# design.net
KiCad netlist of a schematic drawn in Altium Designer
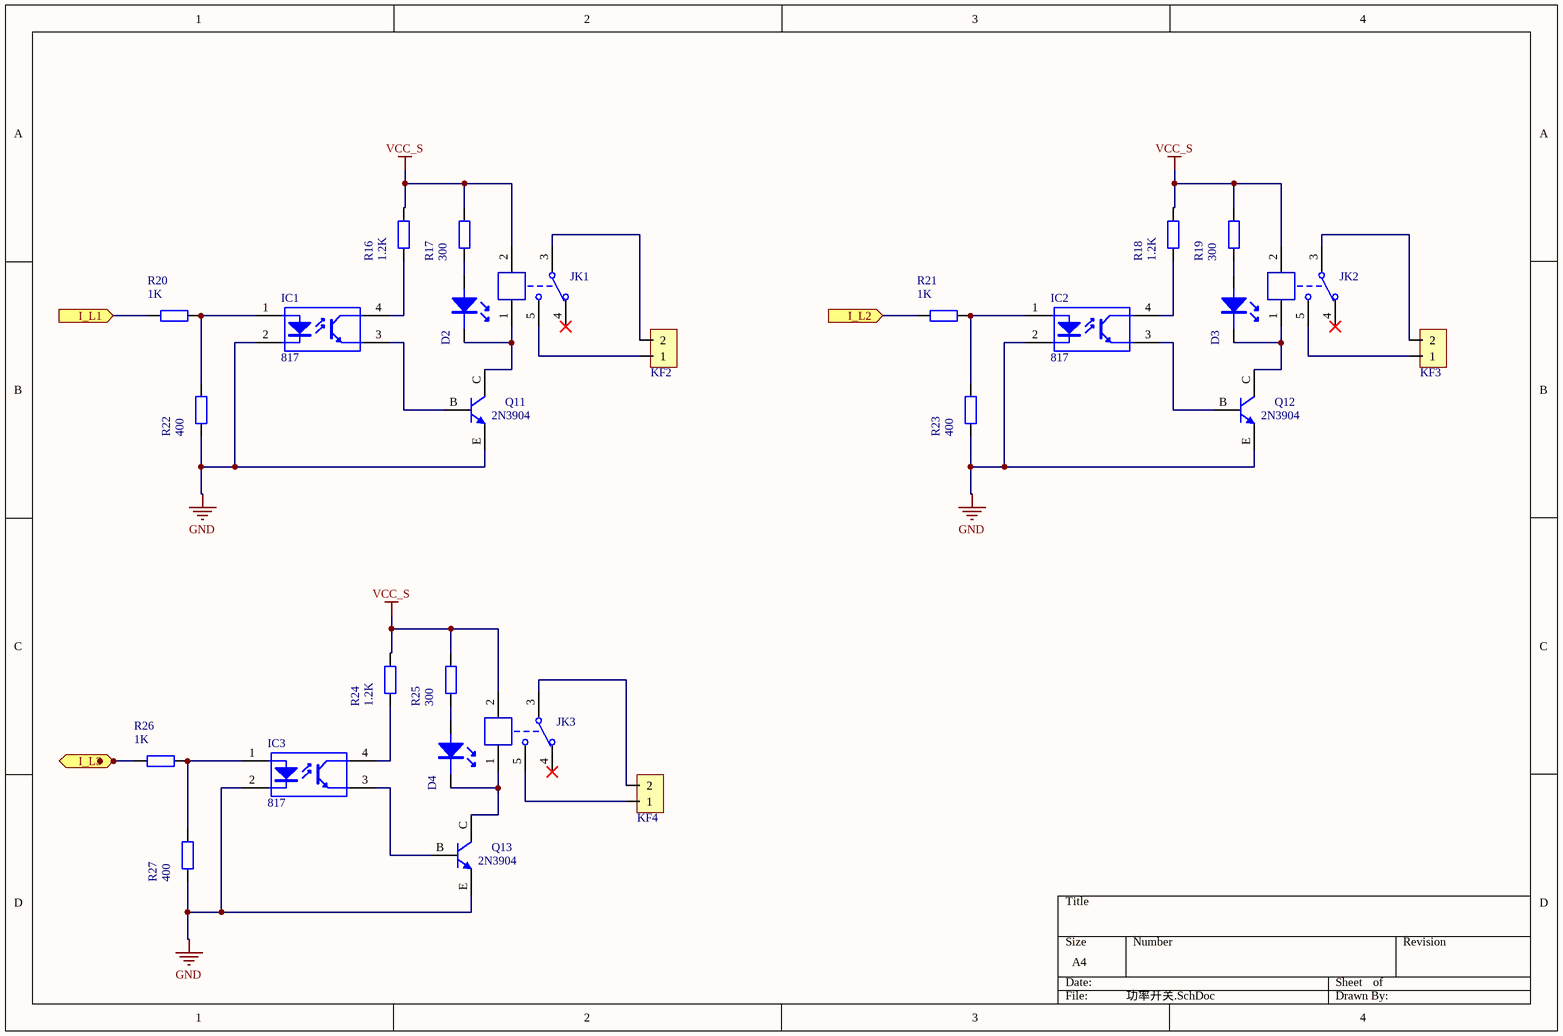
[diagram p0: 功率开关.SchDoc]

(export (version "E")
  (design (tool "Eeschema 10.0.6"))
  (components
    (comp (ref "D2")
      (value "C535A WJN CU0V0231")
      (footprint "LED2-D5X5")
      (description "DIP,封装/间距直径5/2.54mm,额定电压3.2V,亮度高亮,白色")
      (fields
        (field (name "PART NUMBER") "102DL-00002DG.01")
        (field (name "ALLOW ALTENATIVE PART") "Y")
        (field (name "REMARK") "Verified by CRD（张宗良） check list V1.0")
        (field (name "MODIFY TIME") "2017年01月07号")
        (field (name "APPROVED") "YES")
      )
      (libsource (lib "IA-04") (part "Diode-LED-2-N2"))
    )
    (comp (ref "D3")
      (value "C535A WJN CU0V0231")
      (footprint "LED2-D5X5")
      (description "DIP,封装/间距直径5/2.54mm,额定电压3.2V,亮度高亮,白色")
      (fields
        (field (name "PART NUMBER") "102DL-00002DG.01")
        (field (name "ALLOW ALTENATIVE PART") "Y")
        (field (name "REMARK") "Verified by CRD（张宗良） check list V1.0")
        (field (name "MODIFY TIME") "2017年01月07号")
        (field (name "APPROVED") "YES")
      )
      (libsource (lib "IA-04") (part "Diode-LED-2-N2"))
    )
    (comp (ref "D4")
      (value "C535A WJN CU0V0231")
      (footprint "LED2-D5X5")
      (description "DIP,封装/间距直径5/2.54mm,额定电压3.2V,亮度高亮,白色")
      (fields
        (field (name "PART NUMBER") "102DL-00002DG.01")
        (field (name "ALLOW ALTENATIVE PART") "Y")
        (field (name "REMARK") "Verified by CRD（张宗良） check list V1.0")
        (field (name "MODIFY TIME") "2017年01月07号")
        (field (name "APPROVED") "YES")
      )
      (libsource (lib "IA-04") (part "Diode-LED-2-N2"))
    )
    (comp (ref "IC1")
      (value "817")
      (footprint "DIP4-300")
      (description "线性光耦")
      (fields (field (name "版权归属") "源创客"))
      (libsource (lib "11.1 - 传感元件") (part "817"))
    )
    (comp (ref "IC2")
      (value "817")
      (footprint "DIP4-300")
      (description "线性光耦")
      (fields (field (name "版权归属") "源创客"))
      (libsource (lib "11.1 - 传感元件") (part "817"))
    )
    (comp (ref "IC3")
      (value "817")
      (footprint "DIP4-300")
      (description "线性光耦")
      (fields (field (name "版权归属") "源创客"))
      (libsource (lib "11.1 - 传感元件") (part "817"))
    )
    (comp (ref "JK1")
      (value "SRD-05VDC-SL-C")
      (footprint "SRD-C_B")
      (description "5V一组转换")
      (fields (field (name "版权归属") "源创客"))
      (libsource (lib "7.1   - 继电器") (part "SRD-05VDC-SL-C"))
    )
    (comp (ref "JK2")
      (value "SRD-05VDC-SL-C")
      (footprint "SRD-C_B")
      (description "5V一组转换")
      (fields (field (name "版权归属") "源创客"))
      (libsource (lib "7.1   - 继电器") (part "SRD-05VDC-SL-C"))
    )
    (comp (ref "JK3")
      (value "SRD-05VDC-SL-C")
      (footprint "SRD-C_B")
      (description "5V一组转换")
      (fields (field (name "版权归属") "源创客"))
      (libsource (lib "7.1   - 继电器") (part "SRD-05VDC-SL-C"))
    )
    (comp (ref "KF2")
      (value "KF301-5.08-2p")
      (footprint "KF301-5.0-2P")
      (libsource (lib "KF接口") (part "KF301"))
    )
    (comp (ref "KF3")
      (value "KF301-5.08-2p")
      (footprint "KF301-5.0-2P")
      (libsource (lib "KF接口") (part "KF301"))
    )
    (comp (ref "KF4")
      (value "KF301-5.08-2p")
      (footprint "KF301-5.0-2P")
      (libsource (lib "KF接口") (part "KF301"))
    )
    (comp (ref "Q11")
      (value "2N3904")
      (footprint "Triode:TO-92-3-EBC")
      (description "DIP,封装形式TO-92-3,耐压值40V,额定电流200mA,耗散功率625mW")
      (fields
        (field (name "PART NUMBER") "102GN-00009BA.01")
        (field (name "ALLOW ALTENATIVE PART") "Y")
        (field (name "REMARK") "Verified by BU1（吴明徽）check list V1.0")
        (field (name "MODIFY TIME") "2015年08月08号")
        (field (name "APPROVED") "YES")
      )
      (libsource (lib "IA-04") (part "Triode-NPN-BCE"))
    )
    (comp (ref "Q12")
      (value "2N3904")
      (footprint "Triode:TO-92-3-EBC")
      (description "DIP,封装形式TO-92-3,耐压值40V,额定电流200mA,耗散功率625mW")
      (fields
        (field (name "PART NUMBER") "102GN-00009BA.01")
        (field (name "ALLOW ALTENATIVE PART") "Y")
        (field (name "REMARK") "Verified by BU1（吴明徽）check list V1.0")
        (field (name "MODIFY TIME") "2015年08月08号")
        (field (name "APPROVED") "YES")
      )
      (libsource (lib "IA-04") (part "Triode-NPN-BCE"))
    )
    (comp (ref "Q13")
      (value "2N3904")
      (footprint "Triode:TO-92-3-EBC")
      (description "DIP,封装形式TO-92-3,耐压值40V,额定电流200mA,耗散功率625mW")
      (fields
        (field (name "PART NUMBER") "102GN-00009BA.01")
        (field (name "ALLOW ALTENATIVE PART") "Y")
        (field (name "REMARK") "Verified by BU1（吴明徽）check list V1.0")
        (field (name "MODIFY TIME") "2015年08月08号")
        (field (name "APPROVED") "YES")
      )
      (libsource (lib "IA-04") (part "Triode-NPN-BCE"))
    )
    (comp (ref "R16")
      (value "1.2K")
      (footprint "RY0R25W")
      (description "DIP,阻值1K,精度±0.1%,AXIAL0.4,额定功率1/4W")
      (fields
        (field (name "PART NUMBER") "102RO-00085BW.01")
        (field (name "ALLOW ALTENATIVE PART") "Y")
        (field (name "REMARK") "Verified by BU3（吴明徽）check list V1.0")
        (field (name "MODIFY TIME") "2015年11月30号")
        (field (name "APPROVED") "YES")
      )
      (libsource (lib "IA-04") (part "RES-2-NP"))
    )
    (comp (ref "R17")
      (value "300")
      (footprint "RY0R25W")
      (description "DIP,阻值1K,精度±0.1%,AXIAL0.4,额定功率1/4W")
      (fields
        (field (name "PART NUMBER") "102RO-00085BW.01")
        (field (name "ALLOW ALTENATIVE PART") "Y")
        (field (name "REMARK") "Verified by BU3（吴明徽）check list V1.0")
        (field (name "MODIFY TIME") "2015年11月30号")
        (field (name "APPROVED") "YES")
      )
      (libsource (lib "IA-04") (part "RES-2-NP"))
    )
    (comp (ref "R18")
      (value "1.2K")
      (footprint "RY0R25W")
      (description "DIP,阻值1K,精度±0.1%,AXIAL0.4,额定功率1/4W")
      (fields
        (field (name "PART NUMBER") "102RO-00085BW.01")
        (field (name "ALLOW ALTENATIVE PART") "Y")
        (field (name "REMARK") "Verified by BU3（吴明徽）check list V1.0")
        (field (name "MODIFY TIME") "2015年11月30号")
        (field (name "APPROVED") "YES")
      )
      (libsource (lib "IA-04") (part "RES-2-NP"))
    )
    (comp (ref "R19")
      (value "300")
      (footprint "RY0R25W")
      (description "DIP,阻值1K,精度±0.1%,AXIAL0.4,额定功率1/4W")
      (fields
        (field (name "PART NUMBER") "102RO-00085BW.01")
        (field (name "ALLOW ALTENATIVE PART") "Y")
        (field (name "REMARK") "Verified by BU3（吴明徽）check list V1.0")
        (field (name "MODIFY TIME") "2015年11月30号")
        (field (name "APPROVED") "YES")
      )
      (libsource (lib "IA-04") (part "RES-2-NP"))
    )
    (comp (ref "R20")
      (value "1K")
      (footprint "RY0R25W")
      (description "DIP,阻值1K,精度±0.1%,AXIAL0.4,额定功率1/4W")
      (fields
        (field (name "PART NUMBER") "102RO-00085BW.01")
        (field (name "ALLOW ALTENATIVE PART") "Y")
        (field (name "REMARK") "Verified by BU3（吴明徽）check list V1.0")
        (field (name "MODIFY TIME") "2015年11月30号")
        (field (name "APPROVED") "YES")
      )
      (libsource (lib "") (part "RES-2-NP_1"))
    )
    (comp (ref "R21")
      (value "1K")
      (footprint "RY0R25W")
      (description "DIP,阻值1K,精度±0.1%,AXIAL0.4,额定功率1/4W")
      (fields
        (field (name "PART NUMBER") "102RO-00085BW.01")
        (field (name "ALLOW ALTENATIVE PART") "Y")
        (field (name "REMARK") "Verified by BU3（吴明徽）check list V1.0")
        (field (name "MODIFY TIME") "2015年11月30号")
        (field (name "APPROVED") "YES")
      )
      (libsource (lib "") (part "RES-2-NP_1"))
    )
    (comp (ref "R22")
      (value "400")
      (footprint "RY0R25W")
      (description "DIP,阻值1K,精度±0.1%,AXIAL0.4,额定功率1/4W")
      (fields
        (field (name "PART NUMBER") "102RO-00085BW.01")
        (field (name "ALLOW ALTENATIVE PART") "Y")
        (field (name "REMARK") "Verified by BU3（吴明徽）check list V1.0")
        (field (name "MODIFY TIME") "2015年11月30号")
        (field (name "APPROVED") "YES")
      )
      (libsource (lib "IA-04") (part "RES-2-NP"))
    )
    (comp (ref "R23")
      (value "400")
      (footprint "RY0R25W")
      (description "DIP,阻值1K,精度±0.1%,AXIAL0.4,额定功率1/4W")
      (fields
        (field (name "PART NUMBER") "102RO-00085BW.01")
        (field (name "ALLOW ALTENATIVE PART") "Y")
        (field (name "REMARK") "Verified by BU3（吴明徽）check list V1.0")
        (field (name "MODIFY TIME") "2015年11月30号")
        (field (name "APPROVED") "YES")
      )
      (libsource (lib "IA-04") (part "RES-2-NP"))
    )
    (comp (ref "R24")
      (value "1.2K")
      (footprint "RY0R25W")
      (description "DIP,阻值1K,精度±0.1%,AXIAL0.4,额定功率1/4W")
      (fields
        (field (name "PART NUMBER") "102RO-00085BW.01")
        (field (name "ALLOW ALTENATIVE PART") "Y")
        (field (name "REMARK") "Verified by BU3（吴明徽）check list V1.0")
        (field (name "MODIFY TIME") "2015年11月30号")
        (field (name "APPROVED") "YES")
      )
      (libsource (lib "IA-04") (part "RES-2-NP"))
    )
    (comp (ref "R25")
      (value "300")
      (footprint "RY0R25W")
      (description "DIP,阻值1K,精度±0.1%,AXIAL0.4,额定功率1/4W")
      (fields
        (field (name "PART NUMBER") "102RO-00085BW.01")
        (field (name "ALLOW ALTENATIVE PART") "Y")
        (field (name "REMARK") "Verified by BU3（吴明徽）check list V1.0")
        (field (name "MODIFY TIME") "2015年11月30号")
        (field (name "APPROVED") "YES")
      )
      (libsource (lib "IA-04") (part "RES-2-NP"))
    )
    (comp (ref "R26")
      (value "1K")
      (footprint "RY0R25W")
      (description "DIP,阻值1K,精度±0.1%,AXIAL0.4,额定功率1/4W")
      (fields
        (field (name "PART NUMBER") "102RO-00085BW.01")
        (field (name "ALLOW ALTENATIVE PART") "Y")
        (field (name "REMARK") "Verified by BU3（吴明徽）check list V1.0")
        (field (name "MODIFY TIME") "2015年11月30号")
        (field (name "APPROVED") "YES")
      )
      (libsource (lib "") (part "RES-2-NP_1"))
    )
    (comp (ref "R27")
      (value "400")
      (footprint "RY0R25W")
      (description "DIP,阻值1K,精度±0.1%,AXIAL0.4,额定功率1/4W")
      (fields
        (field (name "PART NUMBER") "102RO-00085BW.01")
        (field (name "ALLOW ALTENATIVE PART") "Y")
        (field (name "REMARK") "Verified by BU3（吴明徽）check list V1.0")
        (field (name "MODIFY TIME") "2015年11月30号")
        (field (name "APPROVED") "YES")
      )
      (libsource (lib "IA-04") (part "RES-2-NP"))
    )
  )
  (nets
    (net (code "1") (name "/I_L1") (class "Default")
      (node (ref "R20") (pin "1") (pinfunction "1_1") (pintype "passive"))
    )
    (net (code "2") (name "/I_L2") (class "Default")
      (node (ref "R21") (pin "1") (pinfunction "1_1") (pintype "passive"))
    )
    (net (code "3") (name "/I_L3") (class "Default")
      (node (ref "R26") (pin "1") (pinfunction "1_1") (pintype "passive"))
    )
    (net (code "4") (name "GND") (class "Default")
      (node (ref "IC1") (pin "2") (pinfunction "K_2") (pintype "passive"))
      (node (ref "IC2") (pin "2") (pinfunction "K_2") (pintype "passive"))
      (node (ref "IC3") (pin "2") (pinfunction "K_2") (pintype "passive"))
      (node (ref "Q11") (pin "E") (pinfunction "E_E") (pintype "passive"))
      (node (ref "Q12") (pin "E") (pinfunction "E_E") (pintype "passive"))
      (node (ref "Q13") (pin "E") (pinfunction "E_E") (pintype "passive"))
      (node (ref "R22") (pin "1") (pinfunction "1_1") (pintype "passive"))
      (node (ref "R23") (pin "1") (pinfunction "1_1") (pintype "passive"))
      (node (ref "R27") (pin "1") (pinfunction "1_1") (pintype "passive"))
    )
    (net (code "5") (name "Net-(D2-Pad1)") (class "Default")
      (node (ref "D2") (pin "1") (pinfunction "1_1") (pintype "passive"))
      (node (ref "R17") (pin "1") (pinfunction "1_1") (pintype "passive"))
    )
    (net (code "6") (name "Net-(D2-Pad2)") (class "Default")
      (node (ref "D2") (pin "2") (pinfunction "2_2") (pintype "passive"))
      (node (ref "JK1") (pin "1") (pinfunction "1_1") (pintype "passive"))
      (node (ref "Q11") (pin "C") (pinfunction "C_C") (pintype "passive"))
    )
    (net (code "7") (name "Net-(D3-Pad1)") (class "Default")
      (node (ref "D3") (pin "1") (pinfunction "1_1") (pintype "passive"))
      (node (ref "R19") (pin "1") (pinfunction "1_1") (pintype "passive"))
    )
    (net (code "8") (name "Net-(D3-Pad2)") (class "Default")
      (node (ref "D3") (pin "2") (pinfunction "2_2") (pintype "passive"))
      (node (ref "JK2") (pin "1") (pinfunction "1_1") (pintype "passive"))
      (node (ref "Q12") (pin "C") (pinfunction "C_C") (pintype "passive"))
    )
    (net (code "9") (name "Net-(D4-Pad1)") (class "Default")
      (node (ref "D4") (pin "1") (pinfunction "1_1") (pintype "passive"))
      (node (ref "R25") (pin "1") (pinfunction "1_1") (pintype "passive"))
    )
    (net (code "10") (name "Net-(D4-Pad2)") (class "Default")
      (node (ref "D4") (pin "2") (pinfunction "2_2") (pintype "passive"))
      (node (ref "JK3") (pin "1") (pinfunction "1_1") (pintype "passive"))
      (node (ref "Q13") (pin "C") (pinfunction "C_C") (pintype "passive"))
    )
    (net (code "11") (name "Net-(IC1-A)") (class "Default")
      (node (ref "IC1") (pin "1") (pinfunction "A_1") (pintype "passive"))
      (node (ref "R20") (pin "2") (pinfunction "2_2") (pintype "passive"))
      (node (ref "R22") (pin "2") (pinfunction "2_2") (pintype "passive"))
    )
    (net (code "12") (name "Net-(IC1-C)") (class "Default")
      (node (ref "IC1") (pin "4") (pinfunction "C_4") (pintype "passive"))
      (node (ref "R16") (pin "1") (pinfunction "1_1") (pintype "passive"))
    )
    (net (code "13") (name "Net-(IC1-E)") (class "Default")
      (node (ref "IC1") (pin "3") (pinfunction "E_3") (pintype "passive"))
      (node (ref "Q11") (pin "B") (pinfunction "B_B") (pintype "passive"))
    )
    (net (code "14") (name "Net-(IC2-A)") (class "Default")
      (node (ref "IC2") (pin "1") (pinfunction "A_1") (pintype "passive"))
      (node (ref "R21") (pin "2") (pinfunction "2_2") (pintype "passive"))
      (node (ref "R23") (pin "2") (pinfunction "2_2") (pintype "passive"))
    )
    (net (code "15") (name "Net-(IC2-C)") (class "Default")
      (node (ref "IC2") (pin "4") (pinfunction "C_4") (pintype "passive"))
      (node (ref "R18") (pin "1") (pinfunction "1_1") (pintype "passive"))
    )
    (net (code "16") (name "Net-(IC2-E)") (class "Default")
      (node (ref "IC2") (pin "3") (pinfunction "E_3") (pintype "passive"))
      (node (ref "Q12") (pin "B") (pinfunction "B_B") (pintype "passive"))
    )
    (net (code "17") (name "Net-(IC3-A)") (class "Default")
      (node (ref "IC3") (pin "1") (pinfunction "A_1") (pintype "passive"))
      (node (ref "R26") (pin "2") (pinfunction "2_2") (pintype "passive"))
      (node (ref "R27") (pin "2") (pinfunction "2_2") (pintype "passive"))
    )
    (net (code "18") (name "Net-(IC3-C)") (class "Default")
      (node (ref "IC3") (pin "4") (pinfunction "C_4") (pintype "passive"))
      (node (ref "R24") (pin "1") (pinfunction "1_1") (pintype "passive"))
    )
    (net (code "19") (name "Net-(IC3-E)") (class "Default")
      (node (ref "IC3") (pin "3") (pinfunction "E_3") (pintype "passive"))
      (node (ref "Q13") (pin "B") (pinfunction "B_B") (pintype "passive"))
    )
    (net (code "20") (name "Net-(JK1-Pad3)") (class "Default")
      (node (ref "JK1") (pin "3") (pinfunction "3_3") (pintype "passive"))
      (node (ref "KF2") (pin "2") (pinfunction "2_2") (pintype "passive"))
    )
    (net (code "21") (name "Net-(JK1-Pad5)") (class "Default")
      (node (ref "JK1") (pin "5") (pinfunction "5_5") (pintype "passive"))
      (node (ref "KF2") (pin "1") (pinfunction "1_1") (pintype "passive"))
    )
    (net (code "22") (name "Net-(JK2-Pad3)") (class "Default")
      (node (ref "JK2") (pin "3") (pinfunction "3_3") (pintype "passive"))
      (node (ref "KF3") (pin "2") (pinfunction "2_2") (pintype "passive"))
    )
    (net (code "23") (name "Net-(JK2-Pad5)") (class "Default")
      (node (ref "JK2") (pin "5") (pinfunction "5_5") (pintype "passive"))
      (node (ref "KF3") (pin "1") (pinfunction "1_1") (pintype "passive"))
    )
    (net (code "24") (name "Net-(JK3-Pad3)") (class "Default")
      (node (ref "JK3") (pin "3") (pinfunction "3_3") (pintype "passive"))
      (node (ref "KF4") (pin "2") (pinfunction "2_2") (pintype "passive"))
    )
    (net (code "25") (name "Net-(JK3-Pad5)") (class "Default")
      (node (ref "JK3") (pin "5") (pinfunction "5_5") (pintype "passive"))
      (node (ref "KF4") (pin "1") (pinfunction "1_1") (pintype "passive"))
    )
    (net (code "26") (name "VCC_S") (class "Default")
      (node (ref "JK1") (pin "2") (pinfunction "2_2") (pintype "passive"))
      (node (ref "JK2") (pin "2") (pinfunction "2_2") (pintype "passive"))
      (node (ref "JK3") (pin "2") (pinfunction "2_2") (pintype "passive"))
      (node (ref "R16") (pin "2") (pinfunction "2_2") (pintype "passive"))
      (node (ref "R17") (pin "2") (pinfunction "2_2") (pintype "passive"))
      (node (ref "R18") (pin "2") (pinfunction "2_2") (pintype "passive"))
      (node (ref "R19") (pin "2") (pinfunction "2_2") (pintype "passive"))
      (node (ref "R24") (pin "2") (pinfunction "2_2") (pintype "passive"))
      (node (ref "R25") (pin "2") (pinfunction "2_2") (pintype "passive"))
    )
    (net (code "27") (name "unconnected-(JK1-Pad4)") (class "Default")
      (node (ref "JK1") (pin "4") (pinfunction "4_4") (pintype "passive+no_connect"))
    )
    (net (code "28") (name "unconnected-(JK2-Pad4)") (class "Default")
      (node (ref "JK2") (pin "4") (pinfunction "4_4") (pintype "passive+no_connect"))
    )
    (net (code "29") (name "unconnected-(JK3-Pad4)") (class "Default")
      (node (ref "JK3") (pin "4") (pinfunction "4_4") (pintype "passive+no_connect"))
    )
  )
)
